# peripheralconn.net
KiCad netlist of a schematic drawn in Altium Designer
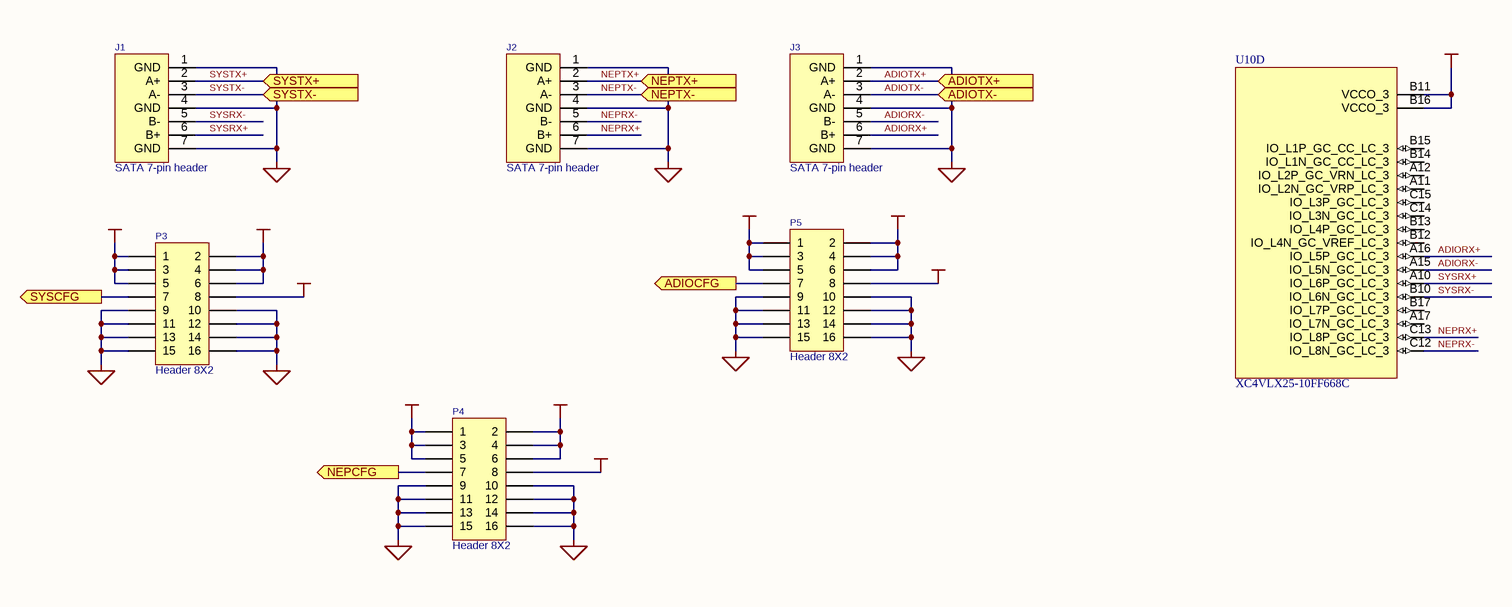
[diagram p0: peripheralconn.SCHDOC]

(export (version "E")
  (design (tool "Eeschema 10.0.6"))
  (components
    (comp (ref "J1")
      (value "SATA 7-pin header")
      (footprint "MOLES 67800-5005")
      (libsource (lib "parts") (part "SATA-7"))
    )
    (comp (ref "J2")
      (value "SATA 7-pin header")
      (footprint "MOLES 67800-5005")
      (libsource (lib "parts") (part "SATA-7"))
    )
    (comp (ref "J3")
      (value "SATA 7-pin header")
      (footprint "MOLES 67800-5005")
      (libsource (lib "parts") (part "SATA-7"))
    )
    (comp (ref "P3")
      (value "Header 8X2")
      (footprint "MOLEX 15-91-2160")
      (description "Header, 8-Pin, Dual row")
      (fields (field (name "PUBLISHER") "Altium Limited"))
      (libsource (lib "parts") (part "Header 8X2"))
    )
    (comp (ref "P4")
      (value "Header 8X2")
      (footprint "MOLEX 15-91-2160")
      (description "Header, 8-Pin, Dual row")
      (fields (field (name "PUBLISHER") "Altium Limited"))
      (libsource (lib "parts") (part "Header 8X2"))
    )
    (comp (ref "P5")
      (value "Header 8X2")
      (footprint "MOLEX 15-91-2160")
      (description "Header, 8-Pin, Dual row")
      (fields (field (name "PUBLISHER") "Altium Limited"))
      (libsource (lib "parts") (part "Header 8X2"))
    )
    (comp (ref "U10")
      (value "XC4VLX25-10FF668C")
      (footprint "Xilinx FF668")
      (description "Xilinx Virtex-4")
      (libsource (lib "parts") (part "XC4VLX25-10FF668C"))
    )
  )
  (nets
    (net (code "1") (name "+2.5VCC") (class "Default")
      (node (ref "U10") (pin "B11") (pinfunction "VCCO_3_B11") (pintype "power_in"))
      (node (ref "U10") (pin "B16") (pinfunction "VCCO_3_B16") (pintype "power_in"))
    )
    (net (code "2") (name "+5VCC") (class "Default")
      (node (ref "P3") (pin "2") (pinfunction "2_2") (pintype "passive"))
      (node (ref "P3") (pin "4") (pinfunction "4_4") (pintype "passive"))
      (node (ref "P3") (pin "6") (pinfunction "6_6") (pintype "passive"))
      (node (ref "P4") (pin "2") (pinfunction "2_2") (pintype "passive"))
      (node (ref "P4") (pin "4") (pinfunction "4_4") (pintype "passive"))
      (node (ref "P4") (pin "6") (pinfunction "6_6") (pintype "passive"))
      (node (ref "P5") (pin "2") (pinfunction "2_2") (pintype "passive"))
      (node (ref "P5") (pin "4") (pinfunction "4_4") (pintype "passive"))
      (node (ref "P5") (pin "6") (pinfunction "6_6") (pintype "passive"))
    )
    (net (code "3") (name "+12VCC") (class "Default")
      (node (ref "P3") (pin "8") (pinfunction "8_8") (pintype "passive"))
      (node (ref "P4") (pin "8") (pinfunction "8_8") (pintype "passive"))
      (node (ref "P5") (pin "8") (pinfunction "8_8") (pintype "passive"))
    )
    (net (code "4") (name "/ADIOCFG") (class "Default")
      (node (ref "P5") (pin "7") (pinfunction "7_7") (pintype "passive"))
    )
    (net (code "5") (name "/ADIORX+") (class "Default")
      (node (ref "J3") (pin "6") (pinfunction "B+_6") (pintype "passive"))
      (node (ref "U10") (pin "A16") (pinfunction "IO_L5P_GC_LC_3_A16") (pintype "bidirectional"))
    )
    (net (code "6") (name "/ADIORX-") (class "Default")
      (node (ref "J3") (pin "5") (pinfunction "B-_5") (pintype "passive"))
      (node (ref "U10") (pin "A15") (pinfunction "IO_L5N_GC_LC_3_A15") (pintype "bidirectional"))
    )
    (net (code "7") (name "/ADIOTX+") (class "Default")
      (node (ref "J3") (pin "2") (pinfunction "A+_2") (pintype "passive"))
    )
    (net (code "8") (name "/ADIOTX-") (class "Default")
      (node (ref "J3") (pin "3") (pinfunction "A-_3") (pintype "passive"))
    )
    (net (code "9") (name "/NEPCFG") (class "Default")
      (node (ref "P4") (pin "7") (pinfunction "7_7") (pintype "passive"))
    )
    (net (code "10") (name "/NEPRX+") (class "Default")
      (node (ref "J2") (pin "6") (pinfunction "B+_6") (pintype "passive"))
      (node (ref "U10") (pin "C13") (pinfunction "IO_L8P_GC_LC_3_C13") (pintype "bidirectional"))
    )
    (net (code "11") (name "/NEPRX-") (class "Default")
      (node (ref "J2") (pin "5") (pinfunction "B-_5") (pintype "passive"))
      (node (ref "U10") (pin "C12") (pinfunction "IO_L8N_GC_LC_3_C12") (pintype "bidirectional"))
    )
    (net (code "12") (name "/NEPTX+") (class "Default")
      (node (ref "J2") (pin "2") (pinfunction "A+_2") (pintype "passive"))
    )
    (net (code "13") (name "/NEPTX-") (class "Default")
      (node (ref "J2") (pin "3") (pinfunction "A-_3") (pintype "passive"))
    )
    (net (code "14") (name "/SYSCFG") (class "Default")
      (node (ref "P3") (pin "7") (pinfunction "7_7") (pintype "passive"))
    )
    (net (code "15") (name "/SYSRX+") (class "Default")
      (node (ref "J1") (pin "6") (pinfunction "B+_6") (pintype "passive"))
      (node (ref "U10") (pin "A10") (pinfunction "IO_L6P_GC_LC_3_A10") (pintype "bidirectional"))
    )
    (net (code "16") (name "/SYSRX-") (class "Default")
      (node (ref "J1") (pin "5") (pinfunction "B-_5") (pintype "passive"))
      (node (ref "U10") (pin "B10") (pinfunction "IO_L6N_GC_LC_3_B10") (pintype "bidirectional"))
    )
    (net (code "17") (name "/SYSTX+") (class "Default")
      (node (ref "J1") (pin "2") (pinfunction "A+_2") (pintype "passive"))
    )
    (net (code "18") (name "/SYSTX-") (class "Default")
      (node (ref "J1") (pin "3") (pinfunction "A-_3") (pintype "passive"))
    )
    (net (code "19") (name "GND") (class "Default")
      (node (ref "J1") (pin "1") (pinfunction "GND_1") (pintype "passive"))
      (node (ref "J1") (pin "4") (pinfunction "GND_4") (pintype "passive"))
      (node (ref "J1") (pin "7") (pinfunction "GND_7") (pintype "passive"))
      (node (ref "J2") (pin "1") (pinfunction "GND_1") (pintype "passive"))
      (node (ref "J2") (pin "4") (pinfunction "GND_4") (pintype "passive"))
      (node (ref "J2") (pin "7") (pinfunction "GND_7") (pintype "passive"))
      (node (ref "J3") (pin "1") (pinfunction "GND_1") (pintype "passive"))
      (node (ref "J3") (pin "4") (pinfunction "GND_4") (pintype "passive"))
      (node (ref "J3") (pin "7") (pinfunction "GND_7") (pintype "passive"))
      (node (ref "P3") (pin "10") (pinfunction "10_10") (pintype "passive"))
      (node (ref "P3") (pin "11") (pinfunction "11_11") (pintype "passive"))
      (node (ref "P3") (pin "12") (pinfunction "12_12") (pintype "passive"))
      (node (ref "P3") (pin "13") (pinfunction "13_13") (pintype "passive"))
      (node (ref "P3") (pin "14") (pinfunction "14_14") (pintype "passive"))
      (node (ref "P3") (pin "15") (pinfunction "15_15") (pintype "passive"))
      (node (ref "P3") (pin "16") (pinfunction "16_16") (pintype "passive"))
      (node (ref "P3") (pin "9") (pinfunction "9_9") (pintype "passive"))
      (node (ref "P4") (pin "10") (pinfunction "10_10") (pintype "passive"))
      (node (ref "P4") (pin "11") (pinfunction "11_11") (pintype "passive"))
      (node (ref "P4") (pin "12") (pinfunction "12_12") (pintype "passive"))
      (node (ref "P4") (pin "13") (pinfunction "13_13") (pintype "passive"))
      (node (ref "P4") (pin "14") (pinfunction "14_14") (pintype "passive"))
      (node (ref "P4") (pin "15") (pinfunction "15_15") (pintype "passive"))
      (node (ref "P4") (pin "16") (pinfunction "16_16") (pintype "passive"))
      (node (ref "P4") (pin "9") (pinfunction "9_9") (pintype "passive"))
      (node (ref "P5") (pin "10") (pinfunction "10_10") (pintype "passive"))
      (node (ref "P5") (pin "11") (pinfunction "11_11") (pintype "passive"))
      (node (ref "P5") (pin "12") (pinfunction "12_12") (pintype "passive"))
      (node (ref "P5") (pin "13") (pinfunction "13_13") (pintype "passive"))
      (node (ref "P5") (pin "14") (pinfunction "14_14") (pintype "passive"))
      (node (ref "P5") (pin "15") (pinfunction "15_15") (pintype "passive"))
      (node (ref "P5") (pin "16") (pinfunction "16_16") (pintype "passive"))
      (node (ref "P5") (pin "9") (pinfunction "9_9") (pintype "passive"))
    )
    (net (code "20") (name "VCC") (class "Default")
      (node (ref "P3") (pin "1") (pinfunction "1_1") (pintype "passive"))
      (node (ref "P3") (pin "3") (pinfunction "3_3") (pintype "passive"))
      (node (ref "P3") (pin "5") (pinfunction "5_5") (pintype "passive"))
      (node (ref "P4") (pin "1") (pinfunction "1_1") (pintype "passive"))
      (node (ref "P4") (pin "3") (pinfunction "3_3") (pintype "passive"))
      (node (ref "P4") (pin "5") (pinfunction "5_5") (pintype "passive"))
      (node (ref "P5") (pin "1") (pinfunction "1_1") (pintype "passive"))
      (node (ref "P5") (pin "3") (pinfunction "3_3") (pintype "passive"))
      (node (ref "P5") (pin "5") (pinfunction "5_5") (pintype "passive"))
    )
    (net (code "21") (name "unconnected-(U10D-IO_L1N_GC_CC_LC_3-PadB14)") (class "Default")
      (node (ref "U10") (pin "B14") (pinfunction "IO_L1N_GC_CC_LC_3_B14") (pintype "bidirectional"))
    )
    (net (code "22") (name "unconnected-(U10D-IO_L1P_GC_CC_LC_3-PadB15)") (class "Default")
      (node (ref "U10") (pin "B15") (pinfunction "IO_L1P_GC_CC_LC_3_B15") (pintype "bidirectional"))
    )
    (net (code "23") (name "unconnected-(U10D-IO_L2N_GC_VRP_LC_3-PadA11)") (class "Default")
      (node (ref "U10") (pin "A11") (pinfunction "IO_L2N_GC_VRP_LC_3_A11") (pintype "bidirectional"))
    )
    (net (code "24") (name "unconnected-(U10D-IO_L2P_GC_VRN_LC_3-PadA12)") (class "Default")
      (node (ref "U10") (pin "A12") (pinfunction "IO_L2P_GC_VRN_LC_3_A12") (pintype "bidirectional"))
    )
    (net (code "25") (name "unconnected-(U10D-IO_L3N_GC_LC_3-PadC14)") (class "Default")
      (node (ref "U10") (pin "C14") (pinfunction "IO_L3N_GC_LC_3_C14") (pintype "bidirectional"))
    )
    (net (code "26") (name "unconnected-(U10D-IO_L3P_GC_LC_3-PadC15)") (class "Default")
      (node (ref "U10") (pin "C15") (pinfunction "IO_L3P_GC_LC_3_C15") (pintype "bidirectional"))
    )
    (net (code "27") (name "unconnected-(U10D-IO_L4N_GC_VREF_LC_3-PadB12)") (class "Default")
      (node (ref "U10") (pin "B12") (pinfunction "IO_L4N_GC_VREF_LC_3_B12") (pintype "bidirectional"))
    )
    (net (code "28") (name "unconnected-(U10D-IO_L4P_GC_LC_3-PadB13)") (class "Default")
      (node (ref "U10") (pin "B13") (pinfunction "IO_L4P_GC_LC_3_B13") (pintype "bidirectional"))
    )
    (net (code "29") (name "unconnected-(U10D-IO_L7N_GC_LC_3-PadA17)") (class "Default")
      (node (ref "U10") (pin "A17") (pinfunction "IO_L7N_GC_LC_3_A17") (pintype "bidirectional"))
    )
    (net (code "30") (name "unconnected-(U10D-IO_L7P_GC_LC_3-PadB17)") (class "Default")
      (node (ref "U10") (pin "B17") (pinfunction "IO_L7P_GC_LC_3_B17") (pintype "bidirectional"))
    )
  )
)
